# PICrouter.net
KiCad netlist of a schematic drawn in EAGLE
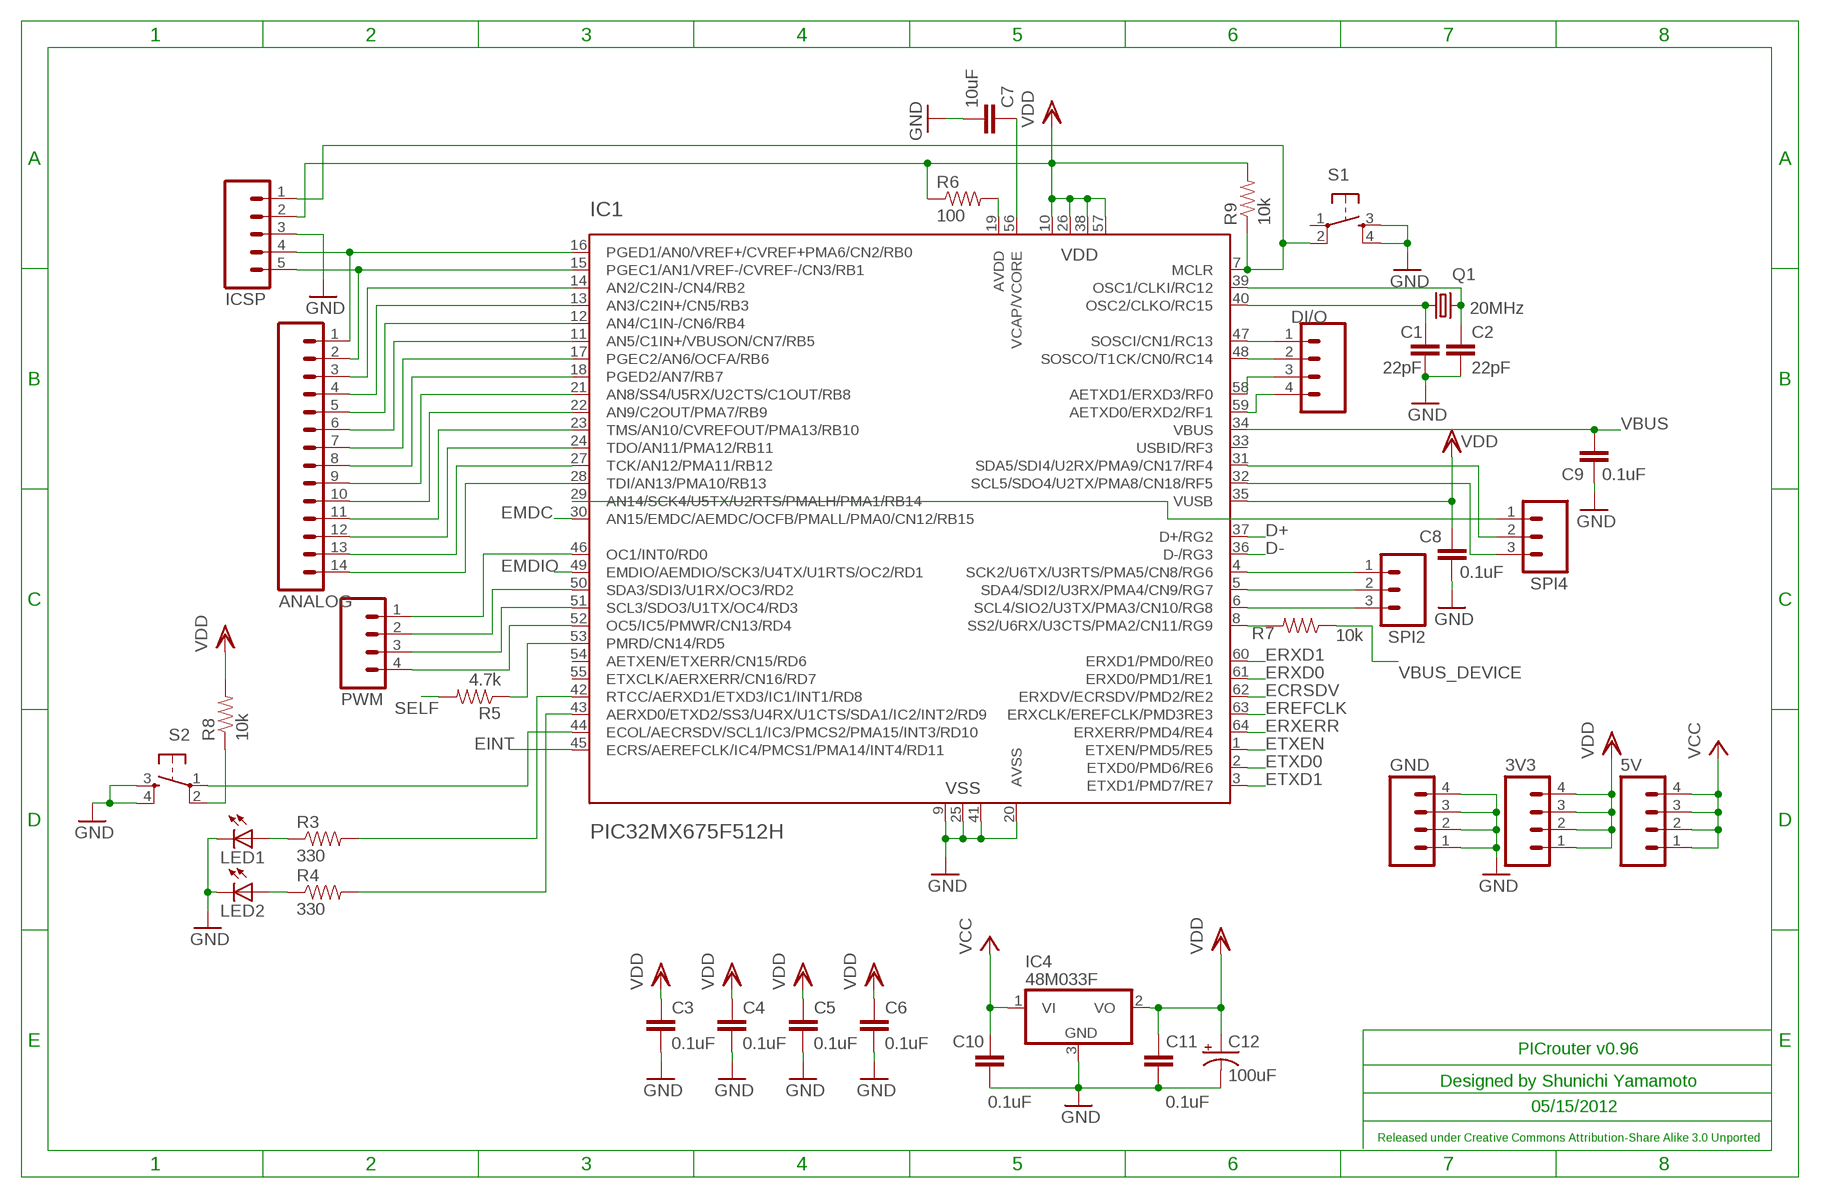
[diagram p0: schematic, sheet 1]
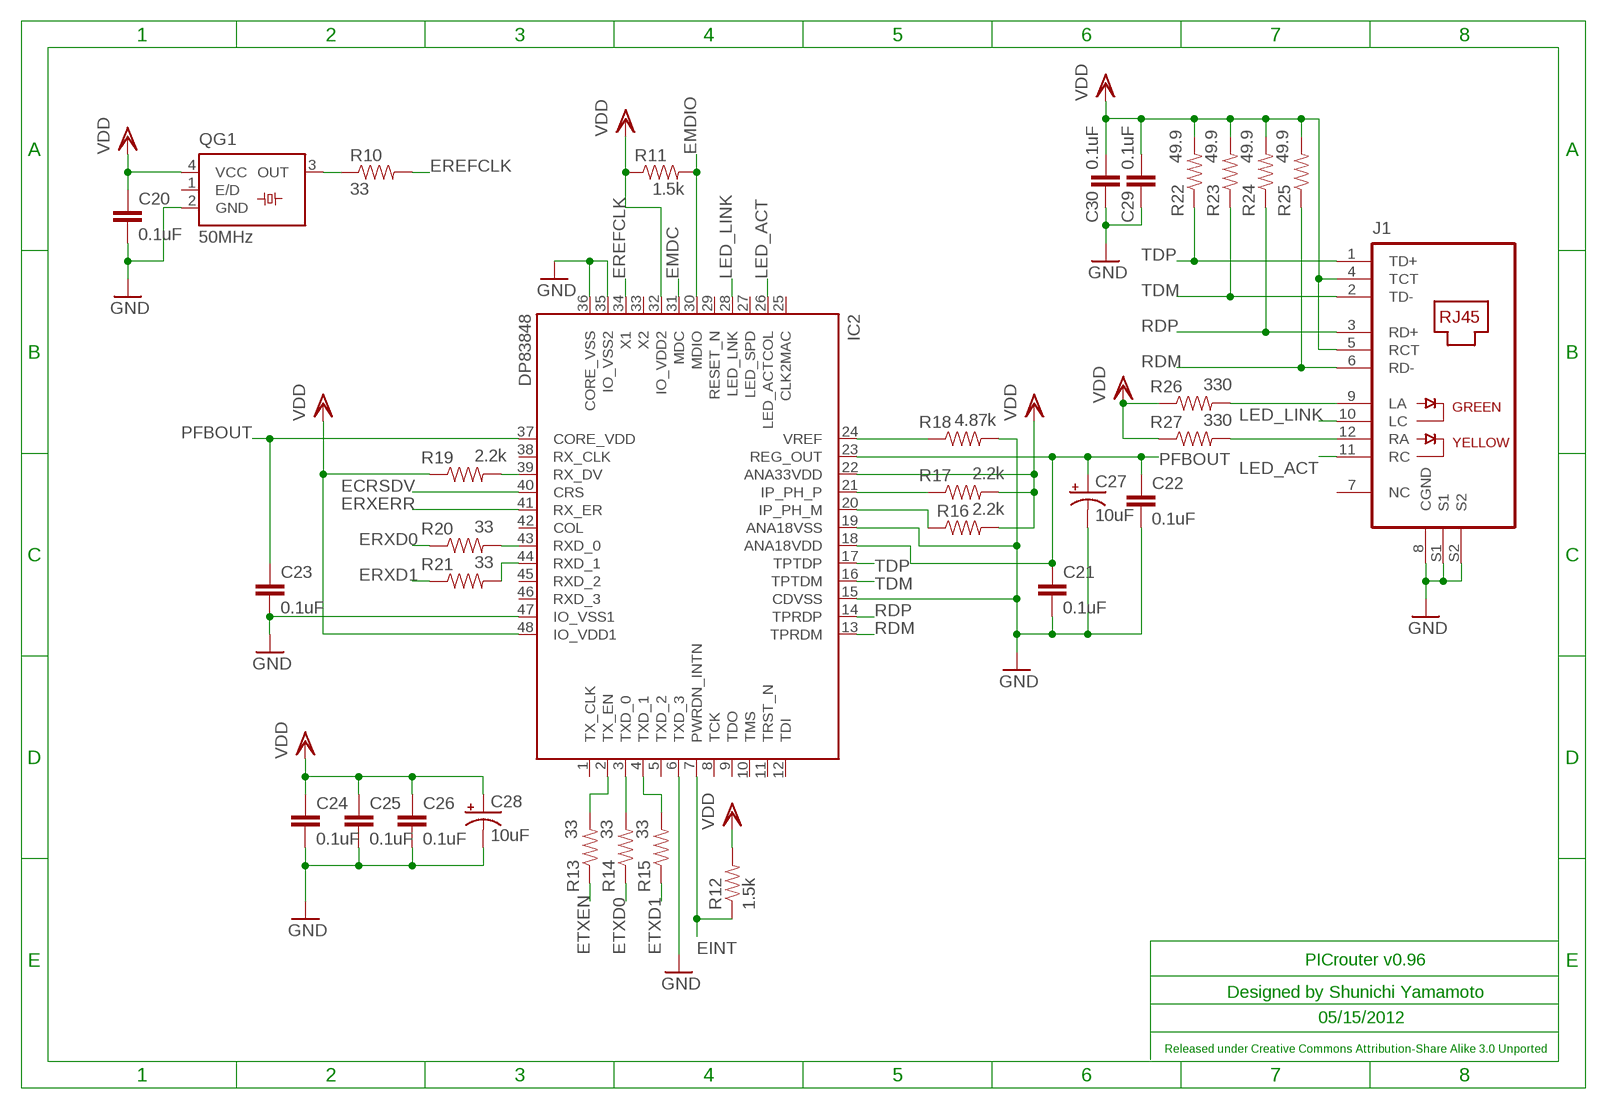
[diagram p1: schematic, sheet 2]
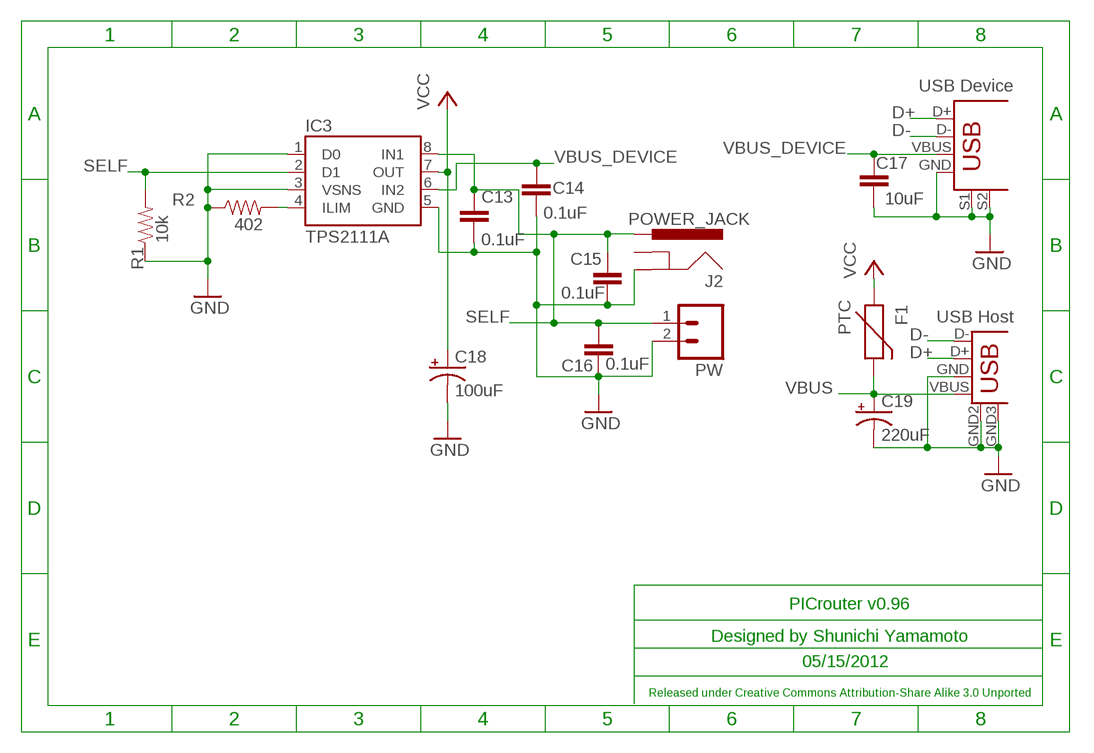
[diagram p2: schematic, sheet 3]

(export (version "E")
  (design (tool "Eeschema 10.0.6"))
  (components
    (comp (ref "C13")
      (value "0.1uF")
      (footprint "eagle-import:C2012")
      (libsource (lib "eagle-import") (part "C-EUC2012"))
    )
    (comp (ref "C14")
      (value "0.1uF")
      (footprint "eagle-import:C2012")
      (libsource (lib "eagle-import") (part "C-EUC2012"))
    )
    (comp (ref "C15")
      (value "0.1uF")
      (footprint "eagle-import:C2012")
      (libsource (lib "eagle-import") (part "C-EUC2012"))
    )
    (comp (ref "C16")
      (value "0.1uF")
      (footprint "eagle-import:C2012")
      (libsource (lib "eagle-import") (part "C-EUC2012"))
    )
    (comp (ref "C17")
      (value "10uF")
      (footprint "eagle-import:C2012")
      (libsource (lib "eagle-import") (part "C-EUC2012"))
    )
    (comp (ref "C18")
      (value "100uF")
      (footprint "eagle-import:PANASONIC_C")
      (libsource (lib "eagle-import") (part "CPOL-USC"))
    )
    (comp (ref "C19")
      (value "220uF")
      (footprint "eagle-import:PANASONIC_D")
      (libsource (lib "eagle-import") (part "CPOL-USD"))
    )
    (comp (ref "F1")
      (value "PTC")
      (footprint "eagle-import:PTC-1206")
      (libsource (lib "eagle-import") (part "PTCSMD"))
    )
    (comp (ref "IC3")
      (value "TPS2111A")
      (footprint "eagle-import:TSSOP8")
      (libsource (lib "eagle-import") (part "TPS2111A"))
    )
    (comp (ref "J2")
      (value "POWER_JACK")
      (footprint "eagle-import:POWER_JACK_PTH_LOCK")
      (libsource (lib "eagle-import") (part "POWER_JACKPTH_LOCK"))
    )
    (comp (ref "PW")
      (value "M02PTH")
      (footprint "eagle-import:1X02")
      (libsource (lib "eagle-import") (part "M02PTH"))
    )
    (comp (ref "R1")
      (value "10k")
      (footprint "eagle-import:0603-RES")
      (libsource (lib "eagle-import") (part "RESISTOR0603-RES"))
    )
    (comp (ref "R2")
      (value "402")
      (footprint "eagle-import:0603-RES")
      (libsource (lib "eagle-import") (part "RESISTOR0603-RES"))
    )
    (comp (ref "U2")
      (value "DEVICE")
      (footprint "eagle-import:USB-B-PTH")
      (libsource (lib "eagle-import") (part "USB+SHIELD"))
    )
    (comp (ref "X2")
      (value "USB-A-H")
      (footprint "eagle-import:USB-A-H")
      (libsource (lib "eagle-import") (part "USB-A-H"))
    )
    (comp (ref "3V3")
      (value "M04PTH")
      (footprint "eagle-import:1X04")
      (libsource (lib "eagle-import") (part "M04PTH"))
    )
    (comp (ref "5V")
      (value "M04PTH")
      (footprint "eagle-import:1X04")
      (libsource (lib "eagle-import") (part "M04PTH"))
    )
    (comp (ref "ANALOG")
      (value "M14")
      (footprint "eagle-import:1X14")
      (libsource (lib "eagle-import") (part "M14"))
    )
    (comp (ref "C1")
      (value "22pF")
      (footprint "eagle-import:C2012")
      (libsource (lib "eagle-import") (part "C-EUC2012"))
    )
    (comp (ref "C2")
      (value "22pF")
      (footprint "eagle-import:C2012")
      (libsource (lib "eagle-import") (part "C-EUC2012"))
    )
    (comp (ref "C3")
      (value "0.1uF")
      (footprint "eagle-import:C2012")
      (libsource (lib "eagle-import") (part "C-EUC2012"))
    )
    (comp (ref "C4")
      (value "0.1uF")
      (footprint "eagle-import:C2012")
      (libsource (lib "eagle-import") (part "C-EUC2012"))
    )
    (comp (ref "C5")
      (value "0.1uF")
      (footprint "eagle-import:C2012")
      (libsource (lib "eagle-import") (part "C-EUC2012"))
    )
    (comp (ref "C6")
      (value "0.1uF")
      (footprint "eagle-import:C2012")
      (libsource (lib "eagle-import") (part "C-EUC2012"))
    )
    (comp (ref "C7")
      (value "10uF")
      (footprint "eagle-import:C2012")
      (libsource (lib "eagle-import") (part "C-EUC2012"))
    )
    (comp (ref "C8")
      (value "0.1uF")
      (footprint "eagle-import:C2012")
      (libsource (lib "eagle-import") (part "C-EUC2012"))
    )
    (comp (ref "C9")
      (value "0.1uF")
      (footprint "eagle-import:C2012")
      (libsource (lib "eagle-import") (part "C-EUC2012"))
    )
    (comp (ref "C10")
      (value "0.1uF")
      (footprint "eagle-import:C2012")
      (libsource (lib "eagle-import") (part "C-EUC2012"))
    )
    (comp (ref "C11")
      (value "0.1uF")
      (footprint "eagle-import:C2012")
      (libsource (lib "eagle-import") (part "C-EUC2012"))
    )
    (comp (ref "C12")
      (value "100uF")
      (footprint "eagle-import:PANASONIC_C")
      (libsource (lib "eagle-import") (part "CPOL-USC"))
    )
    (comp (ref "DI/O")
      (value "M04PTH")
      (footprint "eagle-import:1X04")
      (libsource (lib "eagle-import") (part "M04PTH"))
    )
    (comp (ref "GND")
      (value "M04PTH")
      (footprint "eagle-import:1X04")
      (libsource (lib "eagle-import") (part "M04PTH"))
    )
    (comp (ref "IC1")
      (value "PIC32MX675F512H")
      (footprint "eagle-import:TQFP64-10X10")
      (libsource (lib "eagle-import") (part "PIC32MX675F512H"))
    )
    (comp (ref "IC4")
      (value "48M033F")
      (footprint "eagle-import:TO252")
      (libsource (lib "eagle-import") (part "78DT05"))
    )
    (comp (ref "ICSP")
      (value "M05PTH")
      (footprint "eagle-import:1X05")
      (libsource (lib "eagle-import") (part "M05PTH"))
    )
    (comp (ref "LED1")
      (value "LEDCHIP-LED0603")
      (footprint "eagle-import:CHIP-LED0603")
      (libsource (lib "eagle-import") (part "LEDCHIP-LED0603"))
    )
    (comp (ref "LED2")
      (value "LEDCHIP-LED0603")
      (footprint "eagle-import:CHIP-LED0603")
      (libsource (lib "eagle-import") (part "LEDCHIP-LED0603"))
    )
    (comp (ref "PWM")
      (value "M04PTH")
      (footprint "eagle-import:1X04")
      (libsource (lib "eagle-import") (part "M04PTH"))
    )
    (comp (ref "Q1")
      (value "20MHz")
      (footprint "eagle-import:CTS406")
      (libsource (lib "eagle-import") (part "CRYSTAL"))
    )
    (comp (ref "R3")
      (value "330")
      (footprint "eagle-import:0603-RES")
      (libsource (lib "eagle-import") (part "RESISTOR0603-RES"))
    )
    (comp (ref "R4")
      (value "330")
      (footprint "eagle-import:0603-RES")
      (libsource (lib "eagle-import") (part "RESISTOR0603-RES"))
    )
    (comp (ref "R5")
      (value "4.7k")
      (footprint "eagle-import:0603-RES")
      (libsource (lib "eagle-import") (part "RESISTOR0603-RES"))
    )
    (comp (ref "R6")
      (value "100")
      (footprint "eagle-import:0603-RES")
      (libsource (lib "eagle-import") (part "RESISTOR0603-RES"))
    )
    (comp (ref "R7")
      (value "10k")
      (footprint "eagle-import:0603-RES")
      (libsource (lib "eagle-import") (part "RESISTOR0603-RES"))
    )
    (comp (ref "R8")
      (value "10k")
      (footprint "eagle-import:0603-RES")
      (libsource (lib "eagle-import") (part "RESISTOR0603-RES"))
    )
    (comp (ref "R9")
      (value "10k")
      (footprint "eagle-import:0603-RES")
      (libsource (lib "eagle-import") (part "RESISTOR0603-RES"))
    )
    (comp (ref "S1")
      (value "TAC_SWITCHSMD")
      (footprint "eagle-import:TACTILE_SWITCH_SMD")
      (libsource (lib "eagle-import") (part "TAC_SWITCHSMD"))
    )
    (comp (ref "S2")
      (value "TAC_SWITCHSMD")
      (footprint "eagle-import:TACTILE_SWITCH_SMD")
      (libsource (lib "eagle-import") (part "TAC_SWITCHSMD"))
    )
    (comp (ref "SPI2")
      (value "M03PTH")
      (footprint "eagle-import:1X03")
      (libsource (lib "eagle-import") (part "M03PTH"))
    )
    (comp (ref "SPI4")
      (value "M03PTH")
      (footprint "eagle-import:1X03")
      (libsource (lib "eagle-import") (part "M03PTH"))
    )
    (comp (ref "C20")
      (value "0.1uF")
      (footprint "eagle-import:C2012")
      (libsource (lib "eagle-import") (part "C-EUC2012"))
    )
    (comp (ref "C21")
      (value "0.1uF")
      (footprint "eagle-import:C2012")
      (libsource (lib "eagle-import") (part "C-EUC2012"))
    )
    (comp (ref "C22")
      (value "0.1uF")
      (footprint "eagle-import:C2012")
      (libsource (lib "eagle-import") (part "C-EUC2012"))
    )
    (comp (ref "C23")
      (value "0.1uF")
      (footprint "eagle-import:C2012")
      (libsource (lib "eagle-import") (part "C-EUC2012"))
    )
    (comp (ref "C24")
      (value "0.1uF")
      (footprint "eagle-import:C2012")
      (libsource (lib "eagle-import") (part "C-EUC2012"))
    )
    (comp (ref "C25")
      (value "0.1uF")
      (footprint "eagle-import:C2012")
      (libsource (lib "eagle-import") (part "C-EUC2012"))
    )
    (comp (ref "C26")
      (value "0.1uF")
      (footprint "eagle-import:C2012")
      (libsource (lib "eagle-import") (part "C-EUC2012"))
    )
    (comp (ref "C27")
      (value "10uF")
      (footprint "eagle-import:EIA6032")
      (libsource (lib "eagle-import") (part "CAP_POL6032"))
    )
    (comp (ref "C28")
      (value "10uF")
      (footprint "eagle-import:PANASONIC_C")
      (libsource (lib "eagle-import") (part "CPOL-USC"))
    )
    (comp (ref "C29")
      (value "0.1uF")
      (footprint "eagle-import:C2012")
      (libsource (lib "eagle-import") (part "C-EUC2012"))
    )
    (comp (ref "C30")
      (value "0.1uF")
      (footprint "eagle-import:C2012")
      (libsource (lib "eagle-import") (part "C-EUC2012"))
    )
    (comp (ref "IC2")
      (value "DP83848")
      (footprint "eagle-import:LQFP48")
      (fields (field (name "MPN") "DP83848VYB"))
      (libsource (lib "eagle-import") (part "DP83848"))
    )
    (comp (ref "J1")
      (value "J0011")
      (footprint "eagle-import:PJ-J0")
      (libsource (lib "eagle-import") (part "J0011"))
    )
    (comp (ref "QG1")
      (value "50MHz")
      (footprint "eagle-import:SM77H")
      (libsource (lib "eagle-import") (part "SM77H"))
    )
    (comp (ref "R10")
      (value "33")
      (footprint "eagle-import:0603-RES")
      (libsource (lib "eagle-import") (part "RESISTOR0603-RES"))
    )
    (comp (ref "R11")
      (value "1.5k")
      (footprint "eagle-import:0603-RES")
      (libsource (lib "eagle-import") (part "RESISTOR0603-RES"))
    )
    (comp (ref "R12")
      (value "1.5k")
      (footprint "eagle-import:0603-RES")
      (libsource (lib "eagle-import") (part "RESISTOR0603-RES"))
    )
    (comp (ref "R13")
      (value "33")
      (footprint "eagle-import:0603-RES")
      (libsource (lib "eagle-import") (part "RESISTOR0603-RES"))
    )
    (comp (ref "R14")
      (value "33")
      (footprint "eagle-import:0603-RES")
      (libsource (lib "eagle-import") (part "RESISTOR0603-RES"))
    )
    (comp (ref "R15")
      (value "33")
      (footprint "eagle-import:0603-RES")
      (libsource (lib "eagle-import") (part "RESISTOR0603-RES"))
    )
    (comp (ref "R16")
      (value "2.2k")
      (footprint "eagle-import:0603-RES")
      (libsource (lib "eagle-import") (part "RESISTOR0603-RES"))
    )
    (comp (ref "R17")
      (value "2.2k")
      (footprint "eagle-import:0603-RES")
      (libsource (lib "eagle-import") (part "RESISTOR0603-RES"))
    )
    (comp (ref "R18")
      (value "4.87k")
      (footprint "eagle-import:0603-RES")
      (libsource (lib "eagle-import") (part "RESISTOR0603-RES"))
    )
    (comp (ref "R19")
      (value "2.2k")
      (footprint "eagle-import:0603-RES")
      (libsource (lib "eagle-import") (part "RESISTOR0603-RES"))
    )
    (comp (ref "R20")
      (value "33")
      (footprint "eagle-import:0603-RES")
      (libsource (lib "eagle-import") (part "RESISTOR0603-RES"))
    )
    (comp (ref "R21")
      (value "33")
      (footprint "eagle-import:0603-RES")
      (libsource (lib "eagle-import") (part "RESISTOR0603-RES"))
    )
    (comp (ref "R22")
      (value "49.9")
      (footprint "eagle-import:0603-RES")
      (libsource (lib "eagle-import") (part "RESISTOR0603-RES"))
    )
    (comp (ref "R23")
      (value "49.9")
      (footprint "eagle-import:0603-RES")
      (libsource (lib "eagle-import") (part "RESISTOR0603-RES"))
    )
    (comp (ref "R24")
      (value "49.9")
      (footprint "eagle-import:0603-RES")
      (libsource (lib "eagle-import") (part "RESISTOR0603-RES"))
    )
    (comp (ref "R25")
      (value "49.9")
      (footprint "eagle-import:0603-RES")
      (libsource (lib "eagle-import") (part "RESISTOR0603-RES"))
    )
    (comp (ref "R26")
      (value "330")
      (footprint "eagle-import:0603-RES")
      (libsource (lib "eagle-import") (part "RESISTOR0603-RES"))
    )
    (comp (ref "R27")
      (value "330")
      (footprint "eagle-import:0603-RES")
      (libsource (lib "eagle-import") (part "RESISTOR0603-RES"))
    )
  )
  (nets
    (net (code "1") (name "D+") (class "Default")
      (node (ref "IC1") (pin "37") (pinfunction "D+/RG2_37") (pintype "bidirectional"))
      (node (ref "U2") (pin "D+") (pinfunction "D+_D+") (pintype "bidirectional"))
      (node (ref "X2") (pin "D+") (pinfunction "D+_D+") (pintype "bidirectional"))
    )
    (net (code "2") (name "D-") (class "Default")
      (node (ref "IC1") (pin "36") (pinfunction "D-/RG3_36") (pintype "bidirectional"))
      (node (ref "U2") (pin "D-") (pinfunction "D-_D-") (pintype "bidirectional"))
      (node (ref "X2") (pin "D-") (pinfunction "D-_D-") (pintype "bidirectional"))
    )
    (net (code "3") (name "ECRSDV") (class "Default")
      (node (ref "IC1") (pin "62") (pinfunction "ERXDV/ECRSDV/PMD2/RE2_62") (pintype "bidirectional"))
      (node (ref "IC2") (pin "40") (pinfunction "CRS_40") (pintype "bidirectional"))
    )
    (net (code "4") (name "EINT") (class "Default")
      (node (ref "IC1") (pin "45") (pinfunction "ECRS/AEREFCLK/IC4/PMCS1/PMA14/INT4/RD11_45") (pintype "bidirectional"))
      (node (ref "IC2") (pin "7") (pinfunction "PWRDN_INTN_7") (pintype "bidirectional"))
      (node (ref "R12") (pin "1") (pinfunction "1_1") (pintype "passive"))
    )
    (net (code "5") (name "EMDC") (class "Default")
      (node (ref "IC1") (pin "30") (pinfunction "AN15/EMDC/AEMDC/OCFB/PMALL/PMA0/CN12/RB15_30") (pintype "bidirectional"))
      (node (ref "IC2") (pin "31") (pinfunction "MDC_31") (pintype "input"))
    )
    (net (code "6") (name "EMDIO") (class "Default")
      (node (ref "IC1") (pin "49") (pinfunction "EMDIO/AEMDIO/SCK3/U4TX/U1RTS/OC2/RD1_49") (pintype "bidirectional"))
      (node (ref "IC2") (pin "30") (pinfunction "MDIO_30") (pintype "bidirectional"))
      (node (ref "R11") (pin "2") (pinfunction "2_2") (pintype "passive"))
    )
    (net (code "7") (name "EREFCLK") (class "Default")
      (node (ref "IC1") (pin "63") (pinfunction "ERXCLK/EREFCLK/PMD3RE3_63") (pintype "bidirectional"))
      (node (ref "IC2") (pin "34") (pinfunction "X1_34") (pintype "input"))
      (node (ref "R10") (pin "2") (pinfunction "2_2") (pintype "passive"))
    )
    (net (code "8") (name "ERXD0") (class "Default")
      (node (ref "IC1") (pin "61") (pinfunction "ERXD0/PMD1/RE1_61") (pintype "bidirectional"))
      (node (ref "R20") (pin "1") (pinfunction "1_1") (pintype "passive"))
    )
    (net (code "9") (name "ERXD1") (class "Default")
      (node (ref "IC1") (pin "60") (pinfunction "ERXD1/PMD0/RE0_60") (pintype "bidirectional"))
      (node (ref "R21") (pin "1") (pinfunction "1_1") (pintype "passive"))
    )
    (net (code "10") (name "ERXERR") (class "Default")
      (node (ref "IC1") (pin "64") (pinfunction "ERXERR/PMD4/RE4_64") (pintype "bidirectional"))
      (node (ref "IC2") (pin "41") (pinfunction "RX_ER_41") (pintype "bidirectional"))
    )
    (net (code "11") (name "ETXD0") (class "Default")
      (node (ref "IC1") (pin "2") (pinfunction "ETXD0/PMD6/RE6_2") (pintype "bidirectional"))
      (node (ref "R14") (pin "1") (pinfunction "1_1") (pintype "passive"))
    )
    (net (code "12") (name "ETXD1") (class "Default")
      (node (ref "IC1") (pin "3") (pinfunction "ETXD1/PMD7/RE7_3") (pintype "bidirectional"))
      (node (ref "R15") (pin "1") (pinfunction "1_1") (pintype "passive"))
    )
    (net (code "13") (name "ETXEN") (class "Default")
      (node (ref "IC1") (pin "1") (pinfunction "ETXEN/PMD5/RE5_1") (pintype "bidirectional"))
      (node (ref "R13") (pin "1") (pinfunction "1_1") (pintype "passive"))
    )
    (net (code "14") (name "GND") (class "Default")
      (node (ref "C1") (pin "2") (pinfunction "2_2") (pintype "passive"))
      (node (ref "C10") (pin "2") (pinfunction "2_2") (pintype "passive"))
      (node (ref "C11") (pin "2") (pinfunction "2_2") (pintype "passive"))
      (node (ref "C12") (pin "-") (pinfunction "-_-") (pintype "passive"))
      (node (ref "C13") (pin "2") (pinfunction "2_2") (pintype "passive"))
      (node (ref "C14") (pin "2") (pinfunction "2_2") (pintype "passive"))
      (node (ref "C15") (pin "2") (pinfunction "2_2") (pintype "passive"))
      (node (ref "C16") (pin "2") (pinfunction "2_2") (pintype "passive"))
      (node (ref "C17") (pin "2") (pinfunction "2_2") (pintype "passive"))
      (node (ref "C18") (pin "-") (pinfunction "-_-") (pintype "passive"))
      (node (ref "C19") (pin "-") (pinfunction "-_-") (pintype "passive"))
      (node (ref "C2") (pin "2") (pinfunction "2_2") (pintype "passive"))
      (node (ref "C20") (pin "2") (pinfunction "2_2") (pintype "passive"))
      (node (ref "C21") (pin "2") (pinfunction "2_2") (pintype "passive"))
      (node (ref "C22") (pin "2") (pinfunction "2_2") (pintype "passive"))
      (node (ref "C23") (pin "2") (pinfunction "2_2") (pintype "passive"))
      (node (ref "C24") (pin "2") (pinfunction "2_2") (pintype "passive"))
      (node (ref "C25") (pin "2") (pinfunction "2_2") (pintype "passive"))
      (node (ref "C26") (pin "2") (pinfunction "2_2") (pintype "passive"))
      (node (ref "C27") (pin "P$2") (pinfunction "-_P$2") (pintype "passive"))
      (node (ref "C28") (pin "-") (pinfunction "-_-") (pintype "passive"))
      (node (ref "C29") (pin "2") (pinfunction "2_2") (pintype "passive"))
      (node (ref "C3") (pin "2") (pinfunction "2_2") (pintype "passive"))
      (node (ref "C30") (pin "2") (pinfunction "2_2") (pintype "passive"))
      (node (ref "C4") (pin "2") (pinfunction "2_2") (pintype "passive"))
      (node (ref "C5") (pin "2") (pinfunction "2_2") (pintype "passive"))
      (node (ref "C6") (pin "2") (pinfunction "2_2") (pintype "passive"))
      (node (ref "C7") (pin "2") (pinfunction "2_2") (pintype "passive"))
      (node (ref "C8") (pin "2") (pinfunction "2_2") (pintype "passive"))
      (node (ref "C9") (pin "1") (pinfunction "1_1") (pintype "passive"))
      (node (ref "GND") (pin "1") (pinfunction "1_1") (pintype "passive"))
      (node (ref "GND") (pin "2") (pinfunction "2_2") (pintype "passive"))
      (node (ref "GND") (pin "3") (pinfunction "3_3") (pintype "passive"))
      (node (ref "GND") (pin "4") (pinfunction "4_4") (pintype "passive"))
      (node (ref "IC1") (pin "20") (pinfunction "AVSS_20") (pintype "bidirectional"))
      (node (ref "IC1") (pin "25") (pinfunction "GND_25") (pintype "power_in"))
      (node (ref "IC1") (pin "41") (pinfunction "GND_41") (pintype "power_in"))
      (node (ref "IC1") (pin "9") (pinfunction "GND_9") (pintype "power_in"))
      (node (ref "IC2") (pin "15") (pinfunction "CDVSS_15") (pintype "power_in"))
      (node (ref "IC2") (pin "19") (pinfunction "ANA18VSS_19") (pintype "power_in"))
      (node (ref "IC2") (pin "35") (pinfunction "IO_VSS2_35") (pintype "power_in"))
      (node (ref "IC2") (pin "36") (pinfunction "CORE_VSS_36") (pintype "power_in"))
      (node (ref "IC2") (pin "47") (pinfunction "IO_VSS1_47") (pintype "power_in"))
      (node (ref "IC2") (pin "6") (pinfunction "TXD_3_6") (pintype "bidirectional"))
      (node (ref "IC3") (pin "1") (pinfunction "D0_1") (pintype "input"))
      (node (ref "IC3") (pin "3") (pinfunction "VSNS_3") (pintype "input"))
      (node (ref "IC3") (pin "5") (pinfunction "GND_5") (pintype "power_in"))
      (node (ref "IC4") (pin "3") (pinfunction "GND_3") (pintype "passive"))
      (node (ref "ICSP") (pin "3") (pinfunction "3_3") (pintype "passive"))
      (node (ref "J1") (pin "8") (pinfunction "CGND_8") (pintype "passive"))
      (node (ref "J1") (pin "S1") (pinfunction "S1_S1") (pintype "passive"))
      (node (ref "J1") (pin "S2") (pinfunction "S2_S2") (pintype "passive"))
      (node (ref "J2") (pin "GND") (pinfunction "GND_GND") (pintype "bidirectional"))
      (node (ref "LED1") (pin "C") (pinfunction "C_C") (pintype "passive"))
      (node (ref "LED2") (pin "C") (pinfunction "C_C") (pintype "passive"))
      (node (ref "PW") (pin "2") (pinfunction "2_2") (pintype "passive"))
      (node (ref "QG1") (pin "2") (pinfunction "GND_2") (pintype "power_in"))
      (node (ref "R1") (pin "1") (pinfunction "1_1") (pintype "passive"))
      (node (ref "R18") (pin "2") (pinfunction "2_2") (pintype "passive"))
      (node (ref "R2") (pin "1") (pinfunction "1_1") (pintype "passive"))
      (node (ref "S1") (pin "3") (pinfunction "3_3") (pintype "passive"))
      (node (ref "S1") (pin "4") (pinfunction "4_4") (pintype "passive"))
      (node (ref "S2") (pin "3") (pinfunction "3_3") (pintype "passive"))
      (node (ref "S2") (pin "4") (pinfunction "4_4") (pintype "passive"))
      (node (ref "U2") (pin "GND") (pinfunction "GND_GND") (pintype "bidirectional"))
      (node (ref "U2") (pin "S1") (pinfunction "P$1_S1") (pintype "bidirectional"))
      (node (ref "U2") (pin "S2") (pinfunction "P$2_S2") (pintype "bidirectional"))
      (node (ref "X2") (pin "GND") (pinfunction "GND_GND") (pintype "bidirectional"))
      (node (ref "X2") (pin "GND2") (pinfunction "S1_GND2") (pintype "bidirectional"))
      (node (ref "X2") (pin "GND3") (pinfunction "S2_GND3") (pintype "bidirectional"))
    )
    (net (code "15") (name "LED_ACT") (class "Default")
      (node (ref "IC2") (pin "26") (pinfunction "LED_ACTCOL_26") (pintype "bidirectional"))
      (node (ref "J1") (pin "11") (pinfunction "RC_11") (pintype "passive"))
    )
    (net (code "16") (name "LED_LINK") (class "Default")
      (node (ref "IC2") (pin "28") (pinfunction "LED_LNK_28") (pintype "bidirectional"))
      (node (ref "J1") (pin "10") (pinfunction "LC_10") (pintype "passive"))
    )
    (net (code "17") (name "Net-(IC1-AERXD0{slash}ETXD2{slash}SS3{slash}U4RX{slash}U1CTS{slash}SDA1{slash}IC2{slash}INT2{slash}RD9)") (class "Default")
      (node (ref "IC1") (pin "43") (pinfunction "AERXD0/ETXD2/SS3/U4RX/U1CTS/SDA1/IC2/INT2/RD9_43") (pintype "bidirectional"))
      (node (ref "R4") (pin "2") (pinfunction "2_2") (pintype "passive"))
    )
    (net (code "18") (name "Net-(IC1-AETXD0{slash}ERXD2{slash}RF1)") (class "Default")
      (node (ref "DI/O") (pin "4") (pinfunction "4_4") (pintype "passive"))
      (node (ref "IC1") (pin "59") (pinfunction "AETXD0/ERXD2/RF1_59") (pintype "bidirectional"))
    )
    (net (code "19") (name "Net-(IC1-AETXD1{slash}ERXD3{slash}RF0)") (class "Default")
      (node (ref "DI/O") (pin "3") (pinfunction "3_3") (pintype "passive"))
      (node (ref "IC1") (pin "58") (pinfunction "AETXD1/ERXD3/RF0_58") (pintype "bidirectional"))
    )
    (net (code "20") (name "Net-(IC1-AN2{slash}C2IN-{slash}CN4{slash}RB2)") (class "Default")
      (node (ref "ANALOG") (pin "3") (pinfunction "3_3") (pintype "passive"))
      (node (ref "IC1") (pin "14") (pinfunction "AN2/C2IN-/CN4/RB2_14") (pintype "bidirectional"))
    )
    (net (code "21") (name "Net-(IC1-AN3{slash}C2IN+{slash}CN5{slash}RB3)") (class "Default")
      (node (ref "ANALOG") (pin "4") (pinfunction "4_4") (pintype "passive"))
      (node (ref "IC1") (pin "13") (pinfunction "AN3/C2IN+/CN5/RB3_13") (pintype "bidirectional"))
    )
    (net (code "22") (name "Net-(IC1-AN4{slash}C1IN-{slash}CN6{slash}RB4)") (class "Default")
      (node (ref "ANALOG") (pin "5") (pinfunction "5_5") (pintype "passive"))
      (node (ref "IC1") (pin "12") (pinfunction "AN4/C1IN-/CN6/RB4_12") (pintype "bidirectional"))
    )
    (net (code "23") (name "Net-(IC1-AN5{slash}C1IN+{slash}VBUSON{slash}CN7{slash}RB5)") (class "Default")
      (node (ref "ANALOG") (pin "6") (pinfunction "6_6") (pintype "passive"))
      (node (ref "IC1") (pin "11") (pinfunction "AN5/C1IN+/VBUSON/CN7/RB5_11") (pintype "bidirectional"))
    )
    (net (code "24") (name "Net-(IC1-AN8{slash}SS4{slash}U5RX{slash}U2CTS{slash}C1OUT{slash}RB8)") (class "Default")
      (node (ref "ANALOG") (pin "9") (pinfunction "9_9") (pintype "passive"))
      (node (ref "IC1") (pin "21") (pinfunction "AN8/SS4/U5RX/U2CTS/C1OUT/RB8_21") (pintype "bidirectional"))
    )
    (net (code "25") (name "Net-(IC1-AN9{slash}C2OUT{slash}PMA7{slash}RB9)") (class "Default")
      (node (ref "ANALOG") (pin "10") (pinfunction "10_10") (pintype "passive"))
      (node (ref "IC1") (pin "22") (pinfunction "AN9/C2OUT/PMA7/RB9_22") (pintype "bidirectional"))
    )
    (net (code "26") (name "Net-(IC1-AN14{slash}SCK4{slash}U5TX{slash}U2RTS{slash}PMALH{slash}PMA1{slash}RB14)") (class "Default")
      (node (ref "IC1") (pin "29") (pinfunction "AN14/SCK4/U5TX/U2RTS/PMALH/PMA1/RB14_29") (pintype "bidirectional"))
      (node (ref "SPI4") (pin "1") (pinfunction "1_1") (pintype "passive"))
    )
    (net (code "27") (name "Net-(IC1-AVDD)") (class "Default")
      (node (ref "IC1") (pin "19") (pinfunction "AVDD_19") (pintype "bidirectional"))
      (node (ref "R6") (pin "2") (pinfunction "2_2") (pintype "passive"))
    )
    (net (code "28") (name "Net-(IC1-ECOL{slash}AECRSDV{slash}SCL1{slash}IC3{slash}PMCS2{slash}PMA15{slash}INT3{slash}RD10)") (class "Default")
      (node (ref "IC1") (pin "44") (pinfunction "ECOL/AECRSDV/SCL1/IC3/PMCS2/PMA15/INT3/RD10_44") (pintype "bidirectional"))
      (node (ref "S2") (pin "1") (pinfunction "1_1") (pintype "passive"))
    )
    (net (code "29") (name "Net-(IC1-MCLR)") (class "Default")
      (node (ref "IC1") (pin "7") (pinfunction "MCLR_7") (pintype "bidirectional"))
      (node (ref "ICSP") (pin "1") (pinfunction "1_1") (pintype "passive"))
      (node (ref "R9") (pin "1") (pinfunction "1_1") (pintype "passive"))
      (node (ref "S1") (pin "2") (pinfunction "2_2") (pintype "passive"))
    )
    (net (code "30") (name "Net-(IC1-OC1{slash}INT0{slash}RD0)") (class "Default")
      (node (ref "IC1") (pin "46") (pinfunction "OC1/INT0/RD0_46") (pintype "bidirectional"))
      (node (ref "PWM") (pin "1") (pinfunction "1_1") (pintype "passive"))
    )
    (net (code "31") (name "Net-(IC1-OC5{slash}IC5{slash}PMWR{slash}CN13{slash}RD4)") (class "Default")
      (node (ref "IC1") (pin "52") (pinfunction "OC5/IC5/PMWR/CN13/RD4_52") (pintype "bidirectional"))
      (node (ref "PWM") (pin "4") (pinfunction "4_4") (pintype "passive"))
    )
    (net (code "32") (name "Net-(IC1-OSC1{slash}CLKI{slash}RC12)") (class "Default")
      (node (ref "C2") (pin "1") (pinfunction "1_1") (pintype "passive"))
      (node (ref "IC1") (pin "39") (pinfunction "OSC1/CLKI/RC12_39") (pintype "bidirectional"))
      (node (ref "Q1") (pin "3") (pinfunction "2_3") (pintype "passive"))
    )
    (net (code "33") (name "Net-(IC1-OSC2{slash}CLKO{slash}RC15)") (class "Default")
      (node (ref "C1") (pin "1") (pinfunction "1_1") (pintype "passive"))
      (node (ref "IC1") (pin "40") (pinfunction "OSC2/CLKO/RC15_40") (pintype "bidirectional"))
      (node (ref "Q1") (pin "1") (pinfunction "1_1") (pintype "passive"))
    )
    (net (code "34") (name "Net-(IC1-PGEC1{slash}AN1{slash}VREF-{slash}CVREF-{slash}CN3{slash}RB1)") (class "Default")
      (node (ref "ANALOG") (pin "2") (pinfunction "2_2") (pintype "passive"))
      (node (ref "IC1") (pin "15") (pinfunction "PGEC1/AN1/VREF-/CVREF-/CN3/RB1_15") (pintype "bidirectional"))
      (node (ref "ICSP") (pin "5") (pinfunction "5_5") (pintype "passive"))
    )
    (net (code "35") (name "Net-(IC1-PGEC2{slash}AN6{slash}OCFA{slash}RB6)") (class "Default")
      (node (ref "ANALOG") (pin "7") (pinfunction "7_7") (pintype "passive"))
      (node (ref "IC1") (pin "17") (pinfunction "PGEC2/AN6/OCFA/RB6_17") (pintype "bidirectional"))
    )
    (net (code "36") (name "Net-(IC1-PGED1{slash}AN0{slash}VREF+{slash}CVREF+PMA6{slash}CN2{slash}RB0)") (class "Default")
      (node (ref "ANALOG") (pin "1") (pinfunction "1_1") (pintype "passive"))
      (node (ref "IC1") (pin "16") (pinfunction "PGED1/AN0/VREF+/CVREF+PMA6/CN2/RB0_16") (pintype "bidirectional"))
      (node (ref "ICSP") (pin "4") (pinfunction "4_4") (pintype "passive"))
    )
    (net (code "37") (name "Net-(IC1-PGED2{slash}AN7{slash}RB7)") (class "Default")
      (node (ref "ANALOG") (pin "8") (pinfunction "8_8") (pintype "passive"))
      (node (ref "IC1") (pin "18") (pinfunction "PGED2/AN7/RB7_18") (pintype "bidirectional"))
    )
    (net (code "38") (name "Net-(IC1-PMRD{slash}CN14{slash}RD5)") (class "Default")
      (node (ref "IC1") (pin "53") (pinfunction "PMRD/CN14/RD5_53") (pintype "bidirectional"))
      (node (ref "R5") (pin "1") (pinfunction "1_1") (pintype "passive"))
    )
    (net (code "39") (name "Net-(IC1-RTCC{slash}AERXD1{slash}ETXD3{slash}IC1{slash}INT1{slash}RD8)") (class "Default")
      (node (ref "IC1") (pin "42") (pinfunction "RTCC/AERXD1/ETXD3/IC1/INT1/RD8_42") (pintype "bidirectional"))
      (node (ref "R3") (pin "2") (pinfunction "2_2") (pintype "passive"))
    )
    (net (code "40") (name "Net-(IC1-SCK2{slash}U6TX{slash}U3RTS{slash}PMA5{slash}CN8{slash}RG6)") (class "Default")
      (node (ref "IC1") (pin "4") (pinfunction "SCK2/U6TX/U3RTS/PMA5/CN8/RG6_4") (pintype "bidirectional"))
      (node (ref "SPI2") (pin "1") (pinfunction "1_1") (pintype "passive"))
    )
    (net (code "41") (name "Net-(IC1-SCL3{slash}SDO3{slash}U1TX{slash}OC4{slash}RD3)") (class "Default")
      (node (ref "IC1") (pin "51") (pinfunction "SCL3/SDO3/U1TX/OC4/RD3_51") (pintype "bidirectional"))
      (node (ref "PWM") (pin "3") (pinfunction "3_3") (pintype "passive"))
    )
    (net (code "42") (name "Net-(IC1-SCL4{slash}SIO2{slash}U3TX{slash}PMA3{slash}CN10{slash}RG8)") (class "Default")
      (node (ref "IC1") (pin "6") (pinfunction "SCL4/SIO2/U3TX/PMA3/CN10/RG8_6") (pintype "bidirectional"))
      (node (ref "SPI2") (pin "3") (pinfunction "3_3") (pintype "passive"))
    )
    (net (code "43") (name "Net-(IC1-SCL5{slash}SDO4{slash}U2TX{slash}PMA8{slash}CN18{slash}RF5)") (class "Default")
      (node (ref "IC1") (pin "32") (pinfunction "SCL5/SDO4/U2TX/PMA8/CN18/RF5_32") (pintype "bidirectional"))
      (node (ref "SPI4") (pin "3") (pinfunction "3_3") (pintype "passive"))
    )
    (net (code "44") (name "Net-(IC1-SDA3{slash}SDI3{slash}U1RX{slash}OC3{slash}RD2)") (class "Default")
      (node (ref "IC1") (pin "50") (pinfunction "SDA3/SDI3/U1RX/OC3/RD2_50") (pintype "bidirectional"))
      (node (ref "PWM") (pin "2") (pinfunction "2_2") (pintype "passive"))
    )
    (net (code "45") (name "Net-(IC1-SDA4{slash}SDI2{slash}U3RX{slash}PMA4{slash}CN9{slash}RG7)") (class "Default")
      (node (ref "IC1") (pin "5") (pinfunction "SDA4/SDI2/U3RX/PMA4/CN9/RG7_5") (pintype "bidirectional"))
      (node (ref "SPI2") (pin "2") (pinfunction "2_2") (pintype "passive"))
    )
    (net (code "46") (name "Net-(IC1-SDA5{slash}SDI4{slash}U2RX{slash}PMA9{slash}CN17{slash}RF4)") (class "Default")
      (node (ref "IC1") (pin "31") (pinfunction "SDA5/SDI4/U2RX/PMA9/CN17/RF4_31") (pintype "bidirectional"))
      (node (ref "SPI4") (pin "2") (pinfunction "2_2") (pintype "passive"))
    )
    (net (code "47") (name "Net-(IC1-SOSCI{slash}CN1{slash}RC13)") (class "Default")
      (node (ref "DI/O") (pin "1") (pinfunction "1_1") (pintype "passive"))
      (node (ref "IC1") (pin "47") (pinfunction "SOSCI/CN1/RC13_47") (pintype "bidirectional"))
    )
    (net (code "48") (name "Net-(IC1-SOSCO{slash}T1CK{slash}CN0{slash}RC14)") (class "Default")
      (node (ref "DI/O") (pin "2") (pinfunction "2_2") (pintype "passive"))
      (node (ref "IC1") (pin "48") (pinfunction "SOSCO/T1CK/CN0/RC14_48") (pintype "bidirectional"))
    )
    (net (code "49") (name "Net-(IC1-SS2{slash}U6RX{slash}U3CTS{slash}PMA2{slash}CN11{slash}RG9)") (class "Default")
      (node (ref "IC1") (pin "8") (pinfunction "SS2/U6RX/U3CTS/PMA2/CN11/RG9_8") (pintype "bidirectional"))
      (node (ref "R7") (pin "2") (pinfunction "2_2") (pintype "passive"))
    )
    (net (code "50") (name "Net-(IC1-TCK{slash}AN12{slash}PMA11{slash}RB12)") (class "Default")
      (node (ref "ANALOG") (pin "13") (pinfunction "13_13") (pintype "passive"))
      (node (ref "IC1") (pin "27") (pinfunction "TCK/AN12/PMA11/RB12_27") (pintype "bidirectional"))
    )
    (net (code "51") (name "Net-(IC1-TDI{slash}AN13{slash}PMA10{slash}RB13)") (class "Default")
      (node (ref "ANALOG") (pin "14") (pinfunction "14_14") (pintype "passive"))
      (node (ref "IC1") (pin "28") (pinfunction "TDI/AN13/PMA10/RB13_28") (pintype "bidirectional"))
    )
    (net (code "52") (name "Net-(IC1-TDO{slash}AN11{slash}PMA12{slash}RB11)") (class "Default")
      (node (ref "ANALOG") (pin "12") (pinfunction "12_12") (pintype "passive"))
      (node (ref "IC1") (pin "24") (pinfunction "TDO/AN11/PMA12/RB11_24") (pintype "bidirectional"))
    )
    (net (code "53") (name "Net-(IC1-TMS{slash}AN10{slash}CVREFOUT{slash}PMA13{slash}RB10)") (class "Default")
      (node (ref "ANALOG") (pin "11") (pinfunction "11_11") (pintype "passive"))
      (node (ref "IC1") (pin "23") (pinfunction "TMS/AN10/CVREFOUT/PMA13/RB10_23") (pintype "bidirectional"))
    )
    (net (code "54") (name "Net-(IC1-VCAP{slash}VCORE)") (class "Default")
      (node (ref "C7") (pin "1") (pinfunction "1_1") (pintype "passive"))
      (node (ref "IC1") (pin "56") (pinfunction "VCAP/VCORE_56") (pintype "bidirectional"))
    )
    (net (code "55") (name "Net-(IC2-IP_PH_M)") (class "Default")
      (node (ref "IC2") (pin "20") (pinfunction "IP_PH_M_20") (pintype "input"))
      (node (ref "R16") (pin "1") (pinfunction "1_1") (pintype "passive"))
    )
    (net (code "56") (name "Net-(IC2-IP_PH_P)") (class "Default")
      (node (ref "IC2") (pin "21") (pinfunction "IP_PH_P_21") (pintype "input"))
      (node (ref "R17") (pin "1") (pinfunction "1_1") (pintype "passive"))
    )
    (net (code "57") (name "Net-(IC2-RXD_0)") (class "Default")
      (node (ref "IC2") (pin "43") (pinfunction "RXD_0_43") (pintype "bidirectional"))
      (node (ref "R20") (pin "2") (pinfunction "2_2") (pintype "passive"))
    )
    (net (code "58") (name "Net-(IC2-RXD_1)") (class "Default")
      (node (ref "IC2") (pin "44") (pinfunction "RXD_1_44") (pintype "bidirectional"))
      (node (ref "R21") (pin "2") (pinfunction "2_2") (pintype "passive"))
    )
    (net (code "59") (name "Net-(IC2-RX_DV)") (class "Default")
      (node (ref "IC2") (pin "39") (pinfunction "RX_DV_39") (pintype "bidirectional"))
      (node (ref "R19") (pin "2") (pinfunction "2_2") (pintype "passive"))
    )
    (net (code "60") (name "Net-(IC2-TXD_0)") (class "Default")
      (node (ref "IC2") (pin "3") (pinfunction "TXD_0_3") (pintype "bidirectional"))
      (node (ref "R14") (pin "2") (pinfunction "2_2") (pintype "passive"))
    )
    (net (code "61") (name "Net-(IC2-TXD_1)") (class "Default")
      (node (ref "IC2") (pin "4") (pinfunction "TXD_1_4") (pintype "bidirectional"))
      (node (ref "R15") (pin "2") (pinfunction "2_2") (pintype "passive"))
    )
    (net (code "62") (name "Net-(IC2-TX_EN)") (class "Default")
      (node (ref "IC2") (pin "2") (pinfunction "TX_EN_2") (pintype "bidirectional"))
      (node (ref "R13") (pin "2") (pinfunction "2_2") (pintype "passive"))
    )
    (net (code "63") (name "Net-(IC2-VREF)") (class "Default")
      (node (ref "IC2") (pin "24") (pinfunction "VREF_24") (pintype "bidirectional"))
      (node (ref "R18") (pin "1") (pinfunction "1_1") (pintype "passive"))
    )
    (net (code "64") (name "Net-(IC3-ILIM)") (class "Default")
      (node (ref "IC3") (pin "4") (pinfunction "ILIM_4") (pintype "input"))
      (node (ref "R2") (pin "2") (pinfunction "2_2") (pintype "passive"))
    )
    (net (code "65") (name "Net-(J1-LA)") (class "Default")
      (node (ref "J1") (pin "9") (pinfunction "LA_9") (pintype "passive"))
      (node (ref "R26") (pin "2") (pinfunction "2_2") (pintype "passive"))
    )
    (net (code "66") (name "Net-(J1-RA)") (class "Default")
      (node (ref "J1") (pin "12") (pinfunction "RA_12") (pintype "passive"))
      (node (ref "R27") (pin "2") (pinfunction "2_2") (pintype "passive"))
    )
    (net (code "67") (name "Net-(LED1-PadA)") (class "Default")
      (node (ref "LED1") (pin "A") (pinfunction "A_A") (pintype "passive"))
      (node (ref "R3") (pin "1") (pinfunction "1_1") (pintype "passive"))
    )
    (net (code "68") (name "Net-(LED2-PadA)") (class "Default")
      (node (ref "LED2") (pin "A") (pinfunction "A_A") (pintype "passive"))
      (node (ref "R4") (pin "1") (pinfunction "1_1") (pintype "passive"))
    )
    (net (code "69") (name "Net-(QG1-OUT)") (class "Default")
      (node (ref "QG1") (pin "3") (pinfunction "OUT_3") (pintype "output"))
      (node (ref "R10") (pin "1") (pinfunction "1_1") (pintype "passive"))
    )
    (net (code "70") (name "Net-(R8-Pad1)") (class "Default")
      (node (ref "R8") (pin "1") (pinfunction "1_1") (pintype "passive"))
      (node (ref "S2") (pin "2") (pinfunction "2_2") (pintype "passive"))
    )
    (net (code "71") (name "PFBOUT") (class "Default")
      (node (ref "C21") (pin "1") (pinfunction "1_1") (pintype "passive"))
      (node (ref "C22") (pin "1") (pinfunction "1_1") (pintype "passive"))
      (node (ref "C23") (pin "1") (pinfunction "1_1") (pintype "passive"))
      (node (ref "C27") (pin "P$1") (pinfunction "+_P$1") (pintype "passive"))
      (node (ref "IC2") (pin "18") (pinfunction "ANA18VDD_18") (pintype "power_in"))
      (node (ref "IC2") (pin "23") (pinfunction "REG_OUT_23") (pintype "output"))
      (node (ref "IC2") (pin "37") (pinfunction "CORE_VDD_37") (pintype "power_in"))
    )
    (net (code "72") (name "RDM") (class "Default")
      (node (ref "IC2") (pin "13") (pinfunction "TPRDM_13") (pintype "bidirectional"))
      (node (ref "J1") (pin "6") (pinfunction "RD-_6") (pintype "bidirectional"))
      (node (ref "R25") (pin "1") (pinfunction "1_1") (pintype "passive"))
    )
    (net (code "73") (name "RDP") (class "Default")
      (node (ref "IC2") (pin "14") (pinfunction "TPRDP_14") (pintype "bidirectional"))
      (node (ref "J1") (pin "3") (pinfunction "RD+_3") (pintype "bidirectional"))
      (node (ref "R24") (pin "1") (pinfunction "1_1") (pintype "passive"))
    )
    (net (code "74") (name "SELF") (class "Default")
      (node (ref "C13") (pin "1") (pinfunction "1_1") (pintype "passive"))
      (node (ref "C15") (pin "1") (pinfunction "1_1") (pintype "passive"))
      (node (ref "C16") (pin "1") (pinfunction "1_1") (pintype "passive"))
      (node (ref "IC3") (pin "2") (pinfunction "D1_2") (pintype "input"))
      (node (ref "IC3") (pin "8") (pinfunction "IN1_8") (pintype "input"))
      (node (ref "J2") (pin "PWR") (pinfunction "PWR_PWR") (pintype "bidirectional"))
      (node (ref "PW") (pin "1") (pinfunction "1_1") (pintype "passive"))
      (node (ref "R1") (pin "2") (pinfunction "2_2") (pintype "passive"))
      (node (ref "R5") (pin "2") (pinfunction "2_2") (pintype "passive"))
    )
    (net (code "75") (name "TDM") (class "Default")
      (node (ref "IC2") (pin "16") (pinfunction "TPTDM_16") (pintype "bidirectional"))
      (node (ref "J1") (pin "2") (pinfunction "TD-_2") (pintype "bidirectional"))
      (node (ref "R23") (pin "1") (pinfunction "1_1") (pintype "passive"))
    )
    (net (code "76") (name "TDP") (class "Default")
      (node (ref "IC2") (pin "17") (pinfunction "TPTDP_17") (pintype "bidirectional"))
      (node (ref "J1") (pin "1") (pinfunction "TD+_1") (pintype "bidirectional"))
      (node (ref "R22") (pin "1") (pinfunction "1_1") (pintype "passive"))
    )
    (net (code "77") (name "VBUS") (class "Default")
      (node (ref "C19") (pin "+") (pinfunction "+_+") (pintype "passive"))
      (node (ref "C9") (pin "2") (pinfunction "2_2") (pintype "passive"))
      (node (ref "F1") (pin "2") (pinfunction "2_2") (pintype "bidirectional"))
      (node (ref "IC1") (pin "34") (pinfunction "VBUS_34") (pintype "bidirectional"))
      (node (ref "X2") (pin "VBUS") (pinfunction "VBUS_VBUS") (pintype "bidirectional"))
    )
    (net (code "78") (name "VBUS_DEVICE") (class "Default")
      (node (ref "C14") (pin "1") (pinfunction "1_1") (pintype "passive"))
      (node (ref "C17") (pin "1") (pinfunction "1_1") (pintype "passive"))
      (node (ref "IC3") (pin "6") (pinfunction "IN2_6") (pintype "input"))
      (node (ref "R7") (pin "1") (pinfunction "1_1") (pintype "passive"))
      (node (ref "U2") (pin "VBUS") (pinfunction "VBUS_VBUS") (pintype "bidirectional"))
    )
    (net (code "79") (name "VCC") (class "Default")
      (node (ref "5V") (pin "1") (pinfunction "1_1") (pintype "passive"))
      (node (ref "5V") (pin "2") (pinfunction "2_2") (pintype "passive"))
      (node (ref "5V") (pin "3") (pinfunction "3_3") (pintype "passive"))
      (node (ref "5V") (pin "4") (pinfunction "4_4") (pintype "passive"))
      (node (ref "C10") (pin "1") (pinfunction "1_1") (pintype "passive"))
      (node (ref "C18") (pin "+") (pinfunction "+_+") (pintype "passive"))
      (node (ref "F1") (pin "1") (pinfunction "1_1") (pintype "bidirectional"))
      (node (ref "IC3") (pin "7") (pinfunction "OUT_7") (pintype "output"))
      (node (ref "IC4") (pin "1") (pinfunction "VI_1") (pintype "input"))
    )
    (net (code "80") (name "VDD") (class "Default")
      (node (ref "3V3") (pin "1") (pinfunction "1_1") (pintype "passive"))
      (node (ref "3V3") (pin "2") (pinfunction "2_2") (pintype "passive"))
      (node (ref "3V3") (pin "3") (pinfunction "3_3") (pintype "passive"))
      (node (ref "3V3") (pin "4") (pinfunction "4_4") (pintype "passive"))
      (node (ref "C11") (pin "1") (pinfunction "1_1") (pintype "passive"))
      (node (ref "C12") (pin "+") (pinfunction "+_+") (pintype "passive"))
      (node (ref "C20") (pin "1") (pinfunction "1_1") (pintype "passive"))
      (node (ref "C24") (pin "1") (pinfunction "1_1") (pintype "passive"))
      (node (ref "C25") (pin "1") (pinfunction "1_1") (pintype "passive"))
      (node (ref "C26") (pin "1") (pinfunction "1_1") (pintype "passive"))
      (node (ref "C28") (pin "+") (pinfunction "+_+") (pintype "passive"))
      (node (ref "C29") (pin "1") (pinfunction "1_1") (pintype "passive"))
      (node (ref "C3") (pin "1") (pinfunction "1_1") (pintype "passive"))
      (node (ref "C30") (pin "1") (pinfunction "1_1") (pintype "passive"))
      (node (ref "C4") (pin "1") (pinfunction "1_1") (pintype "passive"))
      (node (ref "C5") (pin "1") (pinfunction "1_1") (pintype "passive"))
      (node (ref "C6") (pin "1") (pinfunction "1_1") (pintype "passive"))
      (node (ref "C8") (pin "1") (pinfunction "1_1") (pintype "passive"))
      (node (ref "IC1") (pin "10") (pinfunction "VDD_10") (pintype "power_in"))
      (node (ref "IC1") (pin "26") (pinfunction "VDD_26") (pintype "power_in"))
      (node (ref "IC1") (pin "35") (pinfunction "VUSB_35") (pintype "bidirectional"))
      (node (ref "IC1") (pin "38") (pinfunction "VDD_38") (pintype "power_in"))
      (node (ref "IC1") (pin "57") (pinfunction "VDD_57") (pintype "power_in"))
      (node (ref "IC2") (pin "22") (pinfunction "ANA33VDD_22") (pintype "power_in"))
      (node (ref "IC2") (pin "32") (pinfunction "IO_VDD2_32") (pintype "power_in"))
      (node (ref "IC2") (pin "48") (pinfunction "IO_VDD1_48") (pintype "power_in"))
      (node (ref "IC4") (pin "2") (pinfunction "VO_2") (pintype "passive"))
      (node (ref "ICSP") (pin "2") (pinfunction "2_2") (pintype "passive"))
      (node (ref "J1") (pin "4") (pinfunction "TCT_4") (pintype "bidirectional"))
      (node (ref "J1") (pin "5") (pinfunction "RCT_5") (pintype "bidirectional"))
      (node (ref "QG1") (pin "4") (pinfunction "VCC_4") (pintype "power_in"))
      (node (ref "R11") (pin "1") (pinfunction "1_1") (pintype "passive"))
      (node (ref "R12") (pin "2") (pinfunction "2_2") (pintype "passive"))
      (node (ref "R16") (pin "2") (pinfunction "2_2") (pintype "passive"))
      (node (ref "R17") (pin "2") (pinfunction "2_2") (pintype "passive"))
      (node (ref "R19") (pin "1") (pinfunction "1_1") (pintype "passive"))
      (node (ref "R22") (pin "2") (pinfunction "2_2") (pintype "passive"))
      (node (ref "R23") (pin "2") (pinfunction "2_2") (pintype "passive"))
      (node (ref "R24") (pin "2") (pinfunction "2_2") (pintype "passive"))
      (node (ref "R25") (pin "2") (pinfunction "2_2") (pintype "passive"))
      (node (ref "R26") (pin "1") (pinfunction "1_1") (pintype "passive"))
      (node (ref "R27") (pin "1") (pinfunction "1_1") (pintype "passive"))
      (node (ref "R6") (pin "1") (pinfunction "1_1") (pintype "passive"))
      (node (ref "R8") (pin "2") (pinfunction "2_2") (pintype "passive"))
      (node (ref "R9") (pin "2") (pinfunction "2_2") (pintype "passive"))
    )
    (net (code "81") (name "unconnected-(IC1-AETXEN{slash}ETXERR{slash}CN15{slash}RD6-Pad54)") (class "Default")
      (node (ref "IC1") (pin "54") (pinfunction "AETXEN/ETXERR/CN15/RD6_54") (pintype "bidirectional"))
    )
    (net (code "82") (name "unconnected-(IC1-ETXCLK{slash}AERXERR{slash}CN16{slash}RD7-Pad55)") (class "Default")
      (node (ref "IC1") (pin "55") (pinfunction "ETXCLK/AERXERR/CN16/RD7_55") (pintype "bidirectional"))
    )
    (net (code "83") (name "unconnected-(IC1-USBID{slash}RF3-Pad33)") (class "Default")
      (node (ref "IC1") (pin "33") (pinfunction "USBID/RF3_33") (pintype "bidirectional"))
    )
    (net (code "84") (name "unconnected-(IC2-CLK2MAC-Pad25)") (class "Default")
      (node (ref "IC2") (pin "25") (pinfunction "CLK2MAC_25") (pintype "bidirectional"))
    )
    (net (code "85") (name "unconnected-(IC2-COL-Pad42)") (class "Default")
      (node (ref "IC2") (pin "42") (pinfunction "COL_42") (pintype "bidirectional"))
    )
    (net (code "86") (name "unconnected-(IC2-LED_SPD-Pad27)") (class "Default")
      (node (ref "IC2") (pin "27") (pinfunction "LED_SPD_27") (pintype "bidirectional"))
    )
    (net (code "87") (name "unconnected-(IC2-RESET_N-Pad29)") (class "Default")
      (node (ref "IC2") (pin "29") (pinfunction "RESET_N_29") (pintype "input"))
    )
    (net (code "88") (name "unconnected-(IC2-RXD_2-Pad45)") (class "Default")
      (node (ref "IC2") (pin "45") (pinfunction "RXD_2_45") (pintype "bidirectional"))
    )
    (net (code "89") (name "unconnected-(IC2-RXD_3-Pad46)") (class "Default")
      (node (ref "IC2") (pin "46") (pinfunction "RXD_3_46") (pintype "bidirectional"))
    )
    (net (code "90") (name "unconnected-(IC2-RX_CLK-Pad38)") (class "Default")
      (node (ref "IC2") (pin "38") (pinfunction "RX_CLK_38") (pintype "bidirectional"))
    )
    (net (code "91") (name "unconnected-(IC2-TCK-Pad8)") (class "Default")
      (node (ref "IC2") (pin "8") (pinfunction "TCK_8") (pintype "input"))
    )
    (net (code "92") (name "unconnected-(IC2-TDI-Pad12)") (class "Default")
      (node (ref "IC2") (pin "12") (pinfunction "TDI_12") (pintype "input"))
    )
    (net (code "93") (name "unconnected-(IC2-TDO-Pad9)") (class "Default")
      (node (ref "IC2") (pin "9") (pinfunction "TDO_9") (pintype "output"))
    )
    (net (code "94") (name "unconnected-(IC2-TMS-Pad10)") (class "Default")
      (node (ref "IC2") (pin "10") (pinfunction "TMS_10") (pintype "input"))
    )
    (net (code "95") (name "unconnected-(IC2-TRST_N-Pad11)") (class "Default")
      (node (ref "IC2") (pin "11") (pinfunction "TRST_N_11") (pintype "input"))
    )
    (net (code "96") (name "unconnected-(IC2-TXD_2-Pad5)") (class "Default")
      (node (ref "IC2") (pin "5") (pinfunction "TXD_2_5") (pintype "bidirectional"))
    )
    (net (code "97") (name "unconnected-(IC2-TX_CLK-Pad1)") (class "Default")
      (node (ref "IC2") (pin "1") (pinfunction "TX_CLK_1") (pintype "bidirectional"))
    )
    (net (code "98") (name "unconnected-(IC2-X2-Pad33)") (class "Default")
      (node (ref "IC2") (pin "33") (pinfunction "X2_33") (pintype "output"))
    )
    (net (code "99") (name "unconnected-(J1-NC-Pad7)") (class "Default")
      (node (ref "J1") (pin "7") (pinfunction "NC_7") (pintype "no_connect"))
    )
    (net (code "100") (name "unconnected-(J2-PadGNDBREAK)") (class "Default")
      (node (ref "J2") (pin "GNDBREAK") (pinfunction "GNDBREAK_GNDBREAK") (pintype "bidirectional"))
    )
    (net (code "101") (name "unconnected-(QG1-E{slash}D-Pad1)") (class "Default")
      (node (ref "QG1") (pin "1") (pinfunction "E/D_1") (pintype "input"))
    )
    (net (code "102") (name "unconnected-(S1-Pad1)") (class "Default")
      (node (ref "S1") (pin "1") (pinfunction "1_1") (pintype "passive"))
    )
  )
)
